# Sheet1.net
KiCad netlist of a schematic drawn in Altium Designer
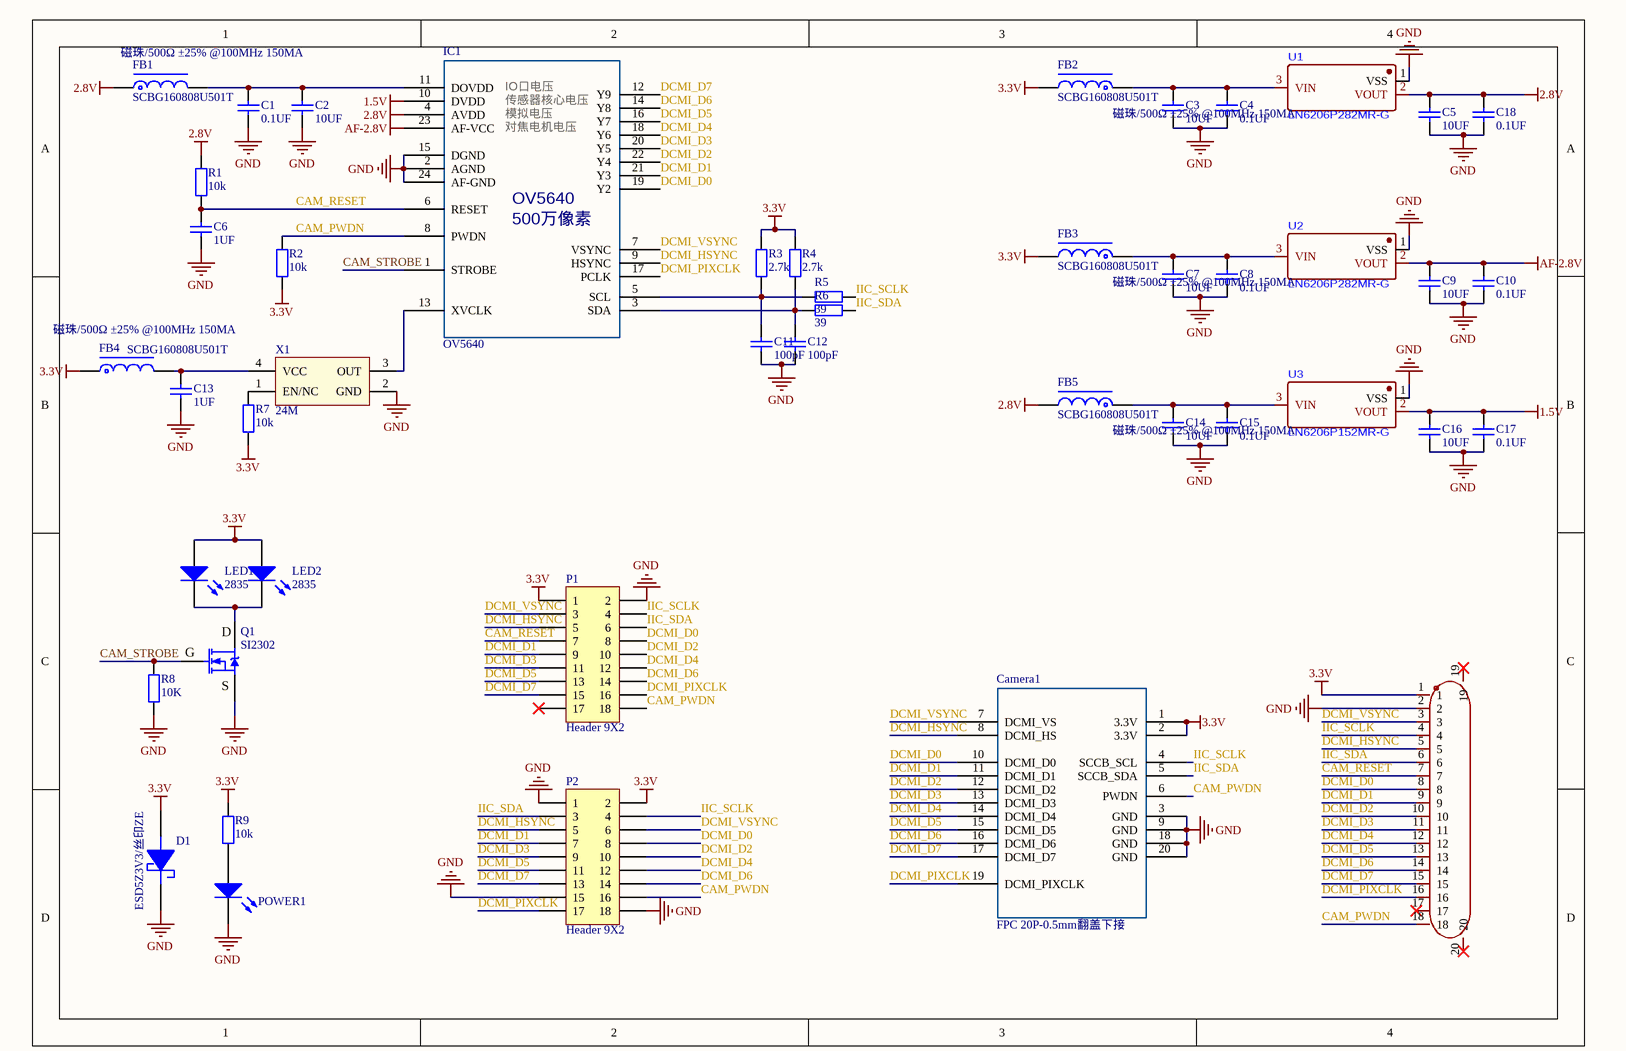
[diagram p0: Sheet1.SchDoc]

(export (version "E")
  (design (tool "Eeschema 10.0.6"))
  (components
    (comp (ref "C1")
      (value "0.1UF")
      (footprint "PCB1:C0603_L")
      (description "贴片电容/MLCC电容")
      (libsource (lib "ov5640") (part "C"))
    )
    (comp (ref "C2")
      (value "10UF")
      (footprint "PCB1:C0603_L")
      (description "贴片电容/MLCC电容")
      (libsource (lib "ov5640") (part "C"))
    )
    (comp (ref "C3")
      (value "10UF")
      (footprint "PCB1:C0603_L")
      (description "贴片电容/MLCC电容")
      (libsource (lib "ov5640") (part "C"))
    )
    (comp (ref "C4")
      (value "0.1UF")
      (footprint "PCB1:C0603_L")
      (description "贴片电容/MLCC电容")
      (libsource (lib "ov5640") (part "C"))
    )
    (comp (ref "C5")
      (value "10UF")
      (footprint "PCB1:C0603_L")
      (description "贴片电容/MLCC电容")
      (libsource (lib "ov5640") (part "C"))
    )
    (comp (ref "C6")
      (value "1UF")
      (footprint "PCB1:C0603_L")
      (description "贴片电容/MLCC电容")
      (libsource (lib "ov5640") (part "C"))
    )
    (comp (ref "C7")
      (value "10UF")
      (footprint "PCB1:C0603_L")
      (description "贴片电容/MLCC电容")
      (libsource (lib "ov5640") (part "C"))
    )
    (comp (ref "C8")
      (value "0.1UF")
      (footprint "PCB1:C0603_L")
      (description "贴片电容/MLCC电容")
      (libsource (lib "ov5640") (part "C"))
    )
    (comp (ref "C9")
      (value "10UF")
      (footprint "PCB1:C0603_L")
      (description "贴片电容/MLCC电容")
      (libsource (lib "ov5640") (part "C"))
    )
    (comp (ref "C10")
      (value "0.1UF")
      (footprint "PCB1:C0603_L")
      (description "贴片电容/MLCC电容")
      (libsource (lib "ov5640") (part "C"))
    )
    (comp (ref "C11")
      (value "100pF")
      (footprint "PCB1:C0603_L")
      (description "贴片电容/MLCC电容")
      (libsource (lib "ov5640") (part "C"))
    )
    (comp (ref "C12")
      (value "100pF")
      (footprint "PCB1:C0603_L")
      (description "贴片电容/MLCC电容")
      (libsource (lib "ov5640") (part "C"))
    )
    (comp (ref "C13")
      (value "1UF")
      (footprint "PCB1:C0603_L")
      (description "贴片电容/MLCC电容")
      (libsource (lib "ov5640") (part "C"))
    )
    (comp (ref "C14")
      (value "10UF")
      (footprint "PCB1:C0603_L")
      (description "贴片电容/MLCC电容")
      (libsource (lib "ov5640") (part "C"))
    )
    (comp (ref "C15")
      (value "0.1UF")
      (footprint "PCB1:C0603_L")
      (description "贴片电容/MLCC电容")
      (libsource (lib "ov5640") (part "C"))
    )
    (comp (ref "C16")
      (value "10UF")
      (footprint "PCB1:C0603_L")
      (description "贴片电容/MLCC电容")
      (libsource (lib "ov5640") (part "C"))
    )
    (comp (ref "C17")
      (value "0.1UF")
      (footprint "PCB1:C0603_L")
      (description "贴片电容/MLCC电容")
      (libsource (lib "ov5640") (part "C"))
    )
    (comp (ref "C18")
      (value "0.1UF")
      (footprint "PCB1:C0603_L")
      (description "贴片电容/MLCC电容")
      (libsource (lib "ov5640") (part "C"))
    )
    (comp (ref "Camera1")
      (value "FPC 20P-0.5mm翻盖下接")
      (footprint "PCB1:FPC20P-0.5MM")
      (libsource (lib "ov5640") (part "FK_Camera"))
    )
    (comp (ref "D1")
      (value "ESD5Z3V3/丝印ZE")
      (footprint "PCB1:SOD523")
      (libsource (lib "ov5640") (part "TVS"))
    )
    (comp (ref "FB1")
      (value "SCBG160808U501T")
      (footprint "PCB1:FB0603")
      (description "贴片磁珠")
      (libsource (lib "ov5640") (part "FB"))
    )
    (comp (ref "FB2")
      (value "SCBG160808U501T")
      (footprint "PCB1:FB0603")
      (description "贴片磁珠")
      (libsource (lib "") (part "FB_1"))
    )
    (comp (ref "FB3")
      (value "SCBG160808U501T")
      (footprint "PCB1:FB0603")
      (description "贴片磁珠")
      (libsource (lib "") (part "FB_1"))
    )
    (comp (ref "FB4")
      (value "SCBG160808U501T")
      (footprint "PCB1:FB0603")
      (description "贴片磁珠")
      (libsource (lib "ov5640") (part "FB"))
    )
    (comp (ref "FB5")
      (value "SCBG160808U501T")
      (footprint "PCB1:FB0603")
      (description "贴片磁珠")
      (libsource (lib "") (part "FB_1"))
    )
    (comp (ref "IC1") (value "OV5640") (footprint "PCB1:OV2640") (libsource (lib "ov5640") (part "OV5640")))
    (comp (ref "LED1")
      (value "2835")
      (footprint "PCB1:LED 2835-2P")
      (description "0.2W 功率LED")
      (libsource (lib "ov5640") (part "LED-2835"))
    )
    (comp (ref "LED2")
      (value "2835")
      (footprint "PCB1:LED 2835-2P")
      (description "0.2W 功率LED")
      (libsource (lib "ov5640") (part "LED-2835"))
    )
    (comp (ref "P1")
      (value "Header 9X2")
      (footprint "PCB1:HDR2X9")
      (description "Header, 9-Pin, Dual row")
      (libsource (lib "ov5640") (part "Header 9X2"))
    )
    (comp (ref "P2")
      (value "Header 9X2")
      (footprint "PCB1:HDR2X9")
      (description "Header, 9-Pin, Dual row")
      (libsource (lib "ov5640") (part "Header 9X2"))
    )
    (comp (ref "POWER1") (value "LED") (footprint "PCB1:D0603") (libsource (lib "ov5640") (part "LED")))
    (comp (ref "Q1")
      (value "SI2302")
      (footprint "PCB1:SOT23-3N")
      (description "N沟道 20V/3A")
      (libsource (lib "ov5640") (part "SI2302"))
    )
    (comp (ref "R1")
      (value "10k")
      (footprint "PCB1:R0603_L")
      (description "贴片电阻")
      (libsource (lib "ov5640") (part "R"))
    )
    (comp (ref "R2")
      (value "10k")
      (footprint "PCB1:R0603_L")
      (description "贴片电阻")
      (libsource (lib "ov5640") (part "R"))
    )
    (comp (ref "R3")
      (value "2.7k")
      (footprint "PCB1:R0603_L")
      (description "贴片电阻")
      (libsource (lib "ov5640") (part "R"))
    )
    (comp (ref "R4")
      (value "2.7k")
      (footprint "PCB1:R0603_L")
      (description "贴片电阻")
      (libsource (lib "ov5640") (part "R"))
    )
    (comp (ref "R5")
      (value "39")
      (footprint "PCB1:R0603_L")
      (description "贴片电阻")
      (libsource (lib "ov5640") (part "R"))
    )
    (comp (ref "R6")
      (value "39")
      (footprint "PCB1:R0603_L")
      (description "贴片电阻")
      (libsource (lib "ov5640") (part "R"))
    )
    (comp (ref "R7")
      (value "10k")
      (footprint "PCB1:R0603_L")
      (description "贴片电阻")
      (libsource (lib "ov5640") (part "R"))
    )
    (comp (ref "R8")
      (value "10K")
      (footprint "PCB1:R0603_L")
      (description "贴片电阻")
      (libsource (lib "ov5640") (part "R"))
    )
    (comp (ref "R9")
      (value "10k")
      (footprint "PCB1:R0603_L")
      (description "贴片电阻")
      (libsource (lib "ov5640") (part "R"))
    )
    (comp (ref "U1")
      (value "LN6206P282MR-G")
      (footprint "PCB1:SOT-23-3_L2.9-W1.3-P1.90-LS2.4-BR")
      (libsource (lib "ov5640") (part "LN6206P282MR-G"))
    )
    (comp (ref "U2")
      (value "LN6206P282MR-G")
      (footprint "PCB1:SOT-23-3_L2.9-W1.3-P1.90-LS2.4-BR")
      (libsource (lib "ov5640") (part "LN6206P282MR-G"))
    )
    (comp (ref "U3")
      (value "LN6206P152MR-G")
      (footprint "PCB1:SOT-23-3_L2.9-W1.3-P1.90-LS2.4-BR")
      (libsource (lib "ov5640") (part "LN6206P282MR-G"))
    )
    (comp (ref "X1")
      (value "24M")
      (footprint "PCB1:OSC-3225-4P")
      (description "4脚有源晶振(振荡器)")
      (libsource (lib "ov5640") (part "XTAL-ACT-4P"))
    )
    (comp (ref "X2")
      (value "AFC07-S18ECA-00")
      (footprint "PCB1:FPC-SMD_AFC07-S18ECA-00")
      (libsource (lib "ov5640") (part "AFC07-S18ECA-00"))
    )
  )
  (nets
    (net (code "1") (name "/CAM_PWDN") (class "Default")
      (node (ref "Camera1") (pin "6") (pinfunction "PWDN_6") (pintype "passive"))
      (node (ref "IC1") (pin "8") (pinfunction "PWDN_8") (pintype "passive"))
      (node (ref "P1") (pin "18") (pinfunction "18_18") (pintype "passive"))
      (node (ref "P2") (pin "16") (pinfunction "16_16") (pintype "passive"))
      (node (ref "R2") (pin "1") (pinfunction "1_1") (pintype "passive"))
      (node (ref "X2") (pin "18") (pinfunction "18_18") (pintype "passive"))
    )
    (net (code "2") (name "/CAM_RESET") (class "Default")
      (node (ref "C6") (pin "2") (pinfunction "2_2") (pintype "passive"))
      (node (ref "IC1") (pin "6") (pinfunction "RESET_6") (pintype "passive"))
      (node (ref "P1") (pin "7") (pinfunction "7_7") (pintype "passive"))
      (node (ref "R1") (pin "2") (pinfunction "2_2") (pintype "passive"))
      (node (ref "X2") (pin "7") (pinfunction "7_7") (pintype "passive"))
    )
    (net (code "3") (name "/CAM_STROBE") (class "Default")
      (node (ref "IC1") (pin "1") (pinfunction "STROBE_1") (pintype "passive"))
      (node (ref "Q1") (pin "1") (pinfunction "G_1") (pintype "passive"))
      (node (ref "R8") (pin "2") (pinfunction "2_2") (pintype "passive"))
    )
    (net (code "4") (name "/DCMI_D0") (class "Default")
      (node (ref "Camera1") (pin "10") (pinfunction "DCMI_D0_10") (pintype "passive"))
      (node (ref "IC1") (pin "19") (pinfunction "Y2_19") (pintype "passive"))
      (node (ref "P1") (pin "8") (pinfunction "8_8") (pintype "passive"))
      (node (ref "P2") (pin "8") (pinfunction "8_8") (pintype "passive"))
      (node (ref "X2") (pin "8") (pinfunction "8_8") (pintype "passive"))
    )
    (net (code "5") (name "/DCMI_D1") (class "Default")
      (node (ref "Camera1") (pin "11") (pinfunction "DCMI_D1_11") (pintype "passive"))
      (node (ref "IC1") (pin "21") (pinfunction "Y3_21") (pintype "passive"))
      (node (ref "P1") (pin "9") (pinfunction "9_9") (pintype "passive"))
      (node (ref "P2") (pin "7") (pinfunction "7_7") (pintype "passive"))
      (node (ref "X2") (pin "9") (pinfunction "9_9") (pintype "passive"))
    )
    (net (code "6") (name "/DCMI_D2") (class "Default")
      (node (ref "Camera1") (pin "12") (pinfunction "DCMI_D2_12") (pintype "passive"))
      (node (ref "IC1") (pin "22") (pinfunction "Y4_22") (pintype "passive"))
      (node (ref "P1") (pin "10") (pinfunction "10_10") (pintype "passive"))
      (node (ref "P2") (pin "10") (pinfunction "10_10") (pintype "passive"))
      (node (ref "X2") (pin "10") (pinfunction "10_10") (pintype "passive"))
    )
    (net (code "7") (name "/DCMI_D3") (class "Default")
      (node (ref "Camera1") (pin "13") (pinfunction "DCMI_D3_13") (pintype "passive"))
      (node (ref "IC1") (pin "20") (pinfunction "Y5_20") (pintype "passive"))
      (node (ref "P1") (pin "11") (pinfunction "11_11") (pintype "passive"))
      (node (ref "P2") (pin "9") (pinfunction "9_9") (pintype "passive"))
      (node (ref "X2") (pin "11") (pinfunction "11_11") (pintype "passive"))
    )
    (net (code "8") (name "/DCMI_D4") (class "Default")
      (node (ref "Camera1") (pin "14") (pinfunction "DCMI_D4_14") (pintype "passive"))
      (node (ref "IC1") (pin "18") (pinfunction "Y6_18") (pintype "passive"))
      (node (ref "P1") (pin "12") (pinfunction "12_12") (pintype "passive"))
      (node (ref "P2") (pin "12") (pinfunction "12_12") (pintype "passive"))
      (node (ref "X2") (pin "12") (pinfunction "12_12") (pintype "passive"))
    )
    (net (code "9") (name "/DCMI_D5") (class "Default")
      (node (ref "Camera1") (pin "15") (pinfunction "DCMI_D5_15") (pintype "passive"))
      (node (ref "IC1") (pin "16") (pinfunction "Y7_16") (pintype "passive"))
      (node (ref "P1") (pin "13") (pinfunction "13_13") (pintype "passive"))
      (node (ref "P2") (pin "11") (pinfunction "11_11") (pintype "passive"))
      (node (ref "X2") (pin "13") (pinfunction "13_13") (pintype "passive"))
    )
    (net (code "10") (name "/DCMI_D6") (class "Default")
      (node (ref "Camera1") (pin "16") (pinfunction "DCMI_D6_16") (pintype "passive"))
      (node (ref "IC1") (pin "14") (pinfunction "Y8_14") (pintype "passive"))
      (node (ref "P1") (pin "14") (pinfunction "14_14") (pintype "passive"))
      (node (ref "P2") (pin "14") (pinfunction "14_14") (pintype "passive"))
      (node (ref "X2") (pin "14") (pinfunction "14_14") (pintype "passive"))
    )
    (net (code "11") (name "/DCMI_D7") (class "Default")
      (node (ref "Camera1") (pin "17") (pinfunction "DCMI_D7_17") (pintype "passive"))
      (node (ref "IC1") (pin "12") (pinfunction "Y9_12") (pintype "passive"))
      (node (ref "P1") (pin "15") (pinfunction "15_15") (pintype "passive"))
      (node (ref "P2") (pin "13") (pinfunction "13_13") (pintype "passive"))
      (node (ref "X2") (pin "15") (pinfunction "15_15") (pintype "passive"))
    )
    (net (code "12") (name "/DCMI_HSYNC") (class "Default")
      (node (ref "Camera1") (pin "8") (pinfunction "DCMI_HS_8") (pintype "passive"))
      (node (ref "IC1") (pin "9") (pinfunction "HSYNC_9") (pintype "passive"))
      (node (ref "P1") (pin "5") (pinfunction "5_5") (pintype "passive"))
      (node (ref "P2") (pin "5") (pinfunction "5_5") (pintype "passive"))
      (node (ref "X2") (pin "5") (pinfunction "5_5") (pintype "passive"))
    )
    (net (code "13") (name "/DCMI_PIXCLK") (class "Default")
      (node (ref "Camera1") (pin "19") (pinfunction "DCMI_PIXCLK_19") (pintype "passive"))
      (node (ref "IC1") (pin "17") (pinfunction "PCLK_17") (pintype "passive"))
      (node (ref "P1") (pin "16") (pinfunction "16_16") (pintype "passive"))
      (node (ref "P2") (pin "17") (pinfunction "17_17") (pintype "passive"))
      (node (ref "X2") (pin "16") (pinfunction "16_16") (pintype "passive"))
    )
    (net (code "14") (name "/DCMI_VSYNC") (class "Default")
      (node (ref "Camera1") (pin "7") (pinfunction "DCMI_VS_7") (pintype "passive"))
      (node (ref "IC1") (pin "7") (pinfunction "VSYNC_7") (pintype "passive"))
      (node (ref "P1") (pin "3") (pinfunction "3_3") (pintype "passive"))
      (node (ref "P2") (pin "6") (pinfunction "6_6") (pintype "passive"))
      (node (ref "X2") (pin "3") (pinfunction "3_3") (pintype "passive"))
    )
    (net (code "15") (name "/IIC_SCLK") (class "Default")
      (node (ref "Camera1") (pin "4") (pinfunction "SCCB_SCL_4") (pintype "passive"))
      (node (ref "P1") (pin "4") (pinfunction "4_4") (pintype "passive"))
      (node (ref "P2") (pin "4") (pinfunction "4_4") (pintype "passive"))
      (node (ref "R5") (pin "2") (pinfunction "2_2") (pintype "passive"))
      (node (ref "X2") (pin "4") (pinfunction "4_4") (pintype "passive"))
    )
    (net (code "16") (name "/IIC_SDA") (class "Default")
      (node (ref "Camera1") (pin "5") (pinfunction "SCCB_SDA_5") (pintype "passive"))
      (node (ref "P1") (pin "6") (pinfunction "6_6") (pintype "passive"))
      (node (ref "P2") (pin "3") (pinfunction "3_3") (pintype "passive"))
      (node (ref "R6") (pin "2") (pinfunction "2_2") (pintype "passive"))
      (node (ref "X2") (pin "6") (pinfunction "6_6") (pintype "passive"))
    )
    (net (code "17") (name "1.5V") (class "Default")
      (node (ref "C16") (pin "2") (pinfunction "2_2") (pintype "passive"))
      (node (ref "C17") (pin "2") (pinfunction "2_2") (pintype "passive"))
      (node (ref "IC1") (pin "10") (pinfunction "DVDD_10") (pintype "passive"))
      (node (ref "U3") (pin "2") (pinfunction "VOUT_2") (pintype "passive"))
    )
    (net (code "18") (name "2.8V") (class "Default")
      (node (ref "C18") (pin "2") (pinfunction "2_2") (pintype "passive"))
      (node (ref "C5") (pin "2") (pinfunction "2_2") (pintype "passive"))
      (node (ref "FB1") (pin "1") (pinfunction "1_1") (pintype "passive"))
      (node (ref "FB5") (pin "2") (pinfunction "2_2") (pintype "passive"))
      (node (ref "IC1") (pin "4") (pinfunction "AVDD_4") (pintype "passive"))
      (node (ref "R1") (pin "1") (pinfunction "1_1") (pintype "passive"))
      (node (ref "U1") (pin "2") (pinfunction "VOUT_2") (pintype "passive"))
    )
    (net (code "19") (name "3.3V") (class "Default")
      (node (ref "Camera1") (pin "1") (pinfunction "3.3V_1") (pintype "passive"))
      (node (ref "Camera1") (pin "2") (pinfunction "3.3V_2") (pintype "passive"))
      (node (ref "D1") (pin "1") (pinfunction "+_1") (pintype "passive"))
      (node (ref "FB2") (pin "2") (pinfunction "2_2") (pintype "passive"))
      (node (ref "FB3") (pin "2") (pinfunction "2_2") (pintype "passive"))
      (node (ref "FB4") (pin "1") (pinfunction "1_1") (pintype "passive"))
      (node (ref "LED1") (pin "1") (pinfunction "A_1") (pintype "passive"))
      (node (ref "LED2") (pin "1") (pinfunction "A_1") (pintype "passive"))
      (node (ref "P1") (pin "1") (pinfunction "1_1") (pintype "passive"))
      (node (ref "P2") (pin "2") (pinfunction "2_2") (pintype "passive"))
      (node (ref "R2") (pin "2") (pinfunction "2_2") (pintype "passive"))
      (node (ref "R3") (pin "2") (pinfunction "2_2") (pintype "passive"))
      (node (ref "R4") (pin "2") (pinfunction "2_2") (pintype "passive"))
      (node (ref "R7") (pin "2") (pinfunction "2_2") (pintype "passive"))
      (node (ref "R9") (pin "2") (pinfunction "2_2") (pintype "passive"))
      (node (ref "X2") (pin "1") (pinfunction "1_1") (pintype "passive"))
    )
    (net (code "20") (name "AF-2.8V") (class "Default")
      (node (ref "C10") (pin "2") (pinfunction "2_2") (pintype "passive"))
      (node (ref "C9") (pin "2") (pinfunction "2_2") (pintype "passive"))
      (node (ref "IC1") (pin "23") (pinfunction "AF-VCC_23") (pintype "passive"))
      (node (ref "U2") (pin "2") (pinfunction "VOUT_2") (pintype "passive"))
    )
    (net (code "21") (name "GND") (class "Default")
      (node (ref "C1") (pin "1") (pinfunction "1_1") (pintype "passive"))
      (node (ref "C10") (pin "1") (pinfunction "1_1") (pintype "passive"))
      (node (ref "C11") (pin "1") (pinfunction "1_1") (pintype "passive"))
      (node (ref "C12") (pin "1") (pinfunction "1_1") (pintype "passive"))
      (node (ref "C13") (pin "1") (pinfunction "1_1") (pintype "passive"))
      (node (ref "C14") (pin "1") (pinfunction "1_1") (pintype "passive"))
      (node (ref "C15") (pin "1") (pinfunction "1_1") (pintype "passive"))
      (node (ref "C16") (pin "1") (pinfunction "1_1") (pintype "passive"))
      (node (ref "C17") (pin "1") (pinfunction "1_1") (pintype "passive"))
      (node (ref "C18") (pin "1") (pinfunction "1_1") (pintype "passive"))
      (node (ref "C2") (pin "1") (pinfunction "1_1") (pintype "passive"))
      (node (ref "C3") (pin "1") (pinfunction "1_1") (pintype "passive"))
      (node (ref "C4") (pin "1") (pinfunction "1_1") (pintype "passive"))
      (node (ref "C5") (pin "1") (pinfunction "1_1") (pintype "passive"))
      (node (ref "C6") (pin "1") (pinfunction "1_1") (pintype "passive"))
      (node (ref "C7") (pin "1") (pinfunction "1_1") (pintype "passive"))
      (node (ref "C8") (pin "1") (pinfunction "1_1") (pintype "passive"))
      (node (ref "C9") (pin "1") (pinfunction "1_1") (pintype "passive"))
      (node (ref "Camera1") (pin "18") (pinfunction "GND_18") (pintype "passive"))
      (node (ref "Camera1") (pin "20") (pinfunction "GND_20") (pintype "passive"))
      (node (ref "Camera1") (pin "3") (pinfunction "GND_3") (pintype "passive"))
      (node (ref "Camera1") (pin "9") (pinfunction "GND_9") (pintype "passive"))
      (node (ref "D1") (pin "2") (pinfunction "-_2") (pintype "passive"))
      (node (ref "IC1") (pin "15") (pinfunction "DGND_15") (pintype "passive"))
      (node (ref "IC1") (pin "2") (pinfunction "AGND_2") (pintype "passive"))
      (node (ref "IC1") (pin "24") (pinfunction "AF-GND_24") (pintype "passive"))
      (node (ref "P1") (pin "2") (pinfunction "2_2") (pintype "passive"))
      (node (ref "P2") (pin "1") (pinfunction "1_1") (pintype "passive"))
      (node (ref "P2") (pin "15") (pinfunction "15_15") (pintype "passive"))
      (node (ref "P2") (pin "18") (pinfunction "18_18") (pintype "passive"))
      (node (ref "POWER1") (pin "2") (pinfunction "K_2") (pintype "passive"))
      (node (ref "Q1") (pin "2") (pinfunction "S_2") (pintype "passive"))
      (node (ref "R8") (pin "1") (pinfunction "1_1") (pintype "passive"))
      (node (ref "U1") (pin "1") (pinfunction "VSS_1") (pintype "passive"))
      (node (ref "U2") (pin "1") (pinfunction "VSS_1") (pintype "passive"))
      (node (ref "U3") (pin "1") (pinfunction "VSS_1") (pintype "passive"))
      (node (ref "X1") (pin "2") (pinfunction "GND_2") (pintype "passive"))
      (node (ref "X2") (pin "2") (pinfunction "2_2") (pintype "passive"))
    )
    (net (code "22") (name "Net-(IC1-DOVDD)") (class "Default")
      (node (ref "C1") (pin "2") (pinfunction "2_2") (pintype "passive"))
      (node (ref "C2") (pin "2") (pinfunction "2_2") (pintype "passive"))
      (node (ref "FB1") (pin "2") (pinfunction "2_2") (pintype "passive"))
      (node (ref "IC1") (pin "11") (pinfunction "DOVDD_11") (pintype "passive"))
    )
    (net (code "23") (name "Net-(IC1-SCL)") (class "Default")
      (node (ref "C11") (pin "2") (pinfunction "2_2") (pintype "passive"))
      (node (ref "IC1") (pin "5") (pinfunction "SCL_5") (pintype "passive"))
      (node (ref "R3") (pin "1") (pinfunction "1_1") (pintype "passive"))
      (node (ref "R5") (pin "1") (pinfunction "1_1") (pintype "passive"))
    )
    (net (code "24") (name "Net-(IC1-SDA)") (class "Default")
      (node (ref "C12") (pin "2") (pinfunction "2_2") (pintype "passive"))
      (node (ref "IC1") (pin "3") (pinfunction "SDA_3") (pintype "passive"))
      (node (ref "R4") (pin "1") (pinfunction "1_1") (pintype "passive"))
      (node (ref "R6") (pin "1") (pinfunction "1_1") (pintype "passive"))
    )
    (net (code "25") (name "Net-(IC1-XVCLK)") (class "Default")
      (node (ref "IC1") (pin "13") (pinfunction "XVCLK_13") (pintype "passive"))
      (node (ref "X1") (pin "3") (pinfunction "OUT_3") (pintype "passive"))
    )
    (net (code "26") (name "Net-(LED1-K)") (class "Default")
      (node (ref "LED1") (pin "2") (pinfunction "K_2") (pintype "passive"))
      (node (ref "LED2") (pin "2") (pinfunction "K_2") (pintype "passive"))
      (node (ref "Q1") (pin "3") (pinfunction "D_3") (pintype "passive"))
    )
    (net (code "27") (name "Net-(POWER1-A)") (class "Default")
      (node (ref "POWER1") (pin "1") (pinfunction "A_1") (pintype "passive"))
      (node (ref "R9") (pin "1") (pinfunction "1_1") (pintype "passive"))
    )
    (net (code "28") (name "Net-(U1-VIN)") (class "Default")
      (node (ref "C3") (pin "2") (pinfunction "2_2") (pintype "passive"))
      (node (ref "C4") (pin "2") (pinfunction "2_2") (pintype "passive"))
      (node (ref "FB2") (pin "1") (pinfunction "1_1") (pintype "passive"))
      (node (ref "U1") (pin "3") (pinfunction "VIN_3") (pintype "passive"))
    )
    (net (code "29") (name "Net-(U2-VIN)") (class "Default")
      (node (ref "C7") (pin "2") (pinfunction "2_2") (pintype "passive"))
      (node (ref "C8") (pin "2") (pinfunction "2_2") (pintype "passive"))
      (node (ref "FB3") (pin "1") (pinfunction "1_1") (pintype "passive"))
      (node (ref "U2") (pin "3") (pinfunction "VIN_3") (pintype "passive"))
    )
    (net (code "30") (name "Net-(U3-VIN)") (class "Default")
      (node (ref "C14") (pin "2") (pinfunction "2_2") (pintype "passive"))
      (node (ref "C15") (pin "2") (pinfunction "2_2") (pintype "passive"))
      (node (ref "FB5") (pin "1") (pinfunction "1_1") (pintype "passive"))
      (node (ref "U3") (pin "3") (pinfunction "VIN_3") (pintype "passive"))
    )
    (net (code "31") (name "Net-(X1-EN{slash}NC)") (class "Default")
      (node (ref "R7") (pin "1") (pinfunction "1_1") (pintype "passive"))
      (node (ref "X1") (pin "1") (pinfunction "EN/NC_1") (pintype "passive"))
    )
    (net (code "32") (name "Net-(X1-VCC)") (class "Default")
      (node (ref "C13") (pin "2") (pinfunction "2_2") (pintype "passive"))
      (node (ref "FB4") (pin "2") (pinfunction "2_2") (pintype "passive"))
      (node (ref "X1") (pin "4") (pinfunction "VCC_4") (pintype "passive"))
    )
    (net (code "33") (name "unconnected-(P1-Pad17)") (class "Default")
      (node (ref "P1") (pin "17") (pinfunction "17_17") (pintype "passive+no_connect"))
    )
    (net (code "34") (name "unconnected-(X2-Pad17)") (class "Default")
      (node (ref "X2") (pin "17") (pinfunction "17_17") (pintype "passive+no_connect"))
    )
    (net (code "35") (name "unconnected-(X2-Pad19)") (class "Default")
      (node (ref "X2") (pin "19") (pinfunction "19_19") (pintype "passive+no_connect"))
    )
    (net (code "36") (name "unconnected-(X2-Pad20)") (class "Default")
      (node (ref "X2") (pin "20") (pinfunction "20_20") (pintype "passive+no_connect"))
    )
  )
)
